# Logic.net
KiCad netlist of a schematic drawn in EAGLE
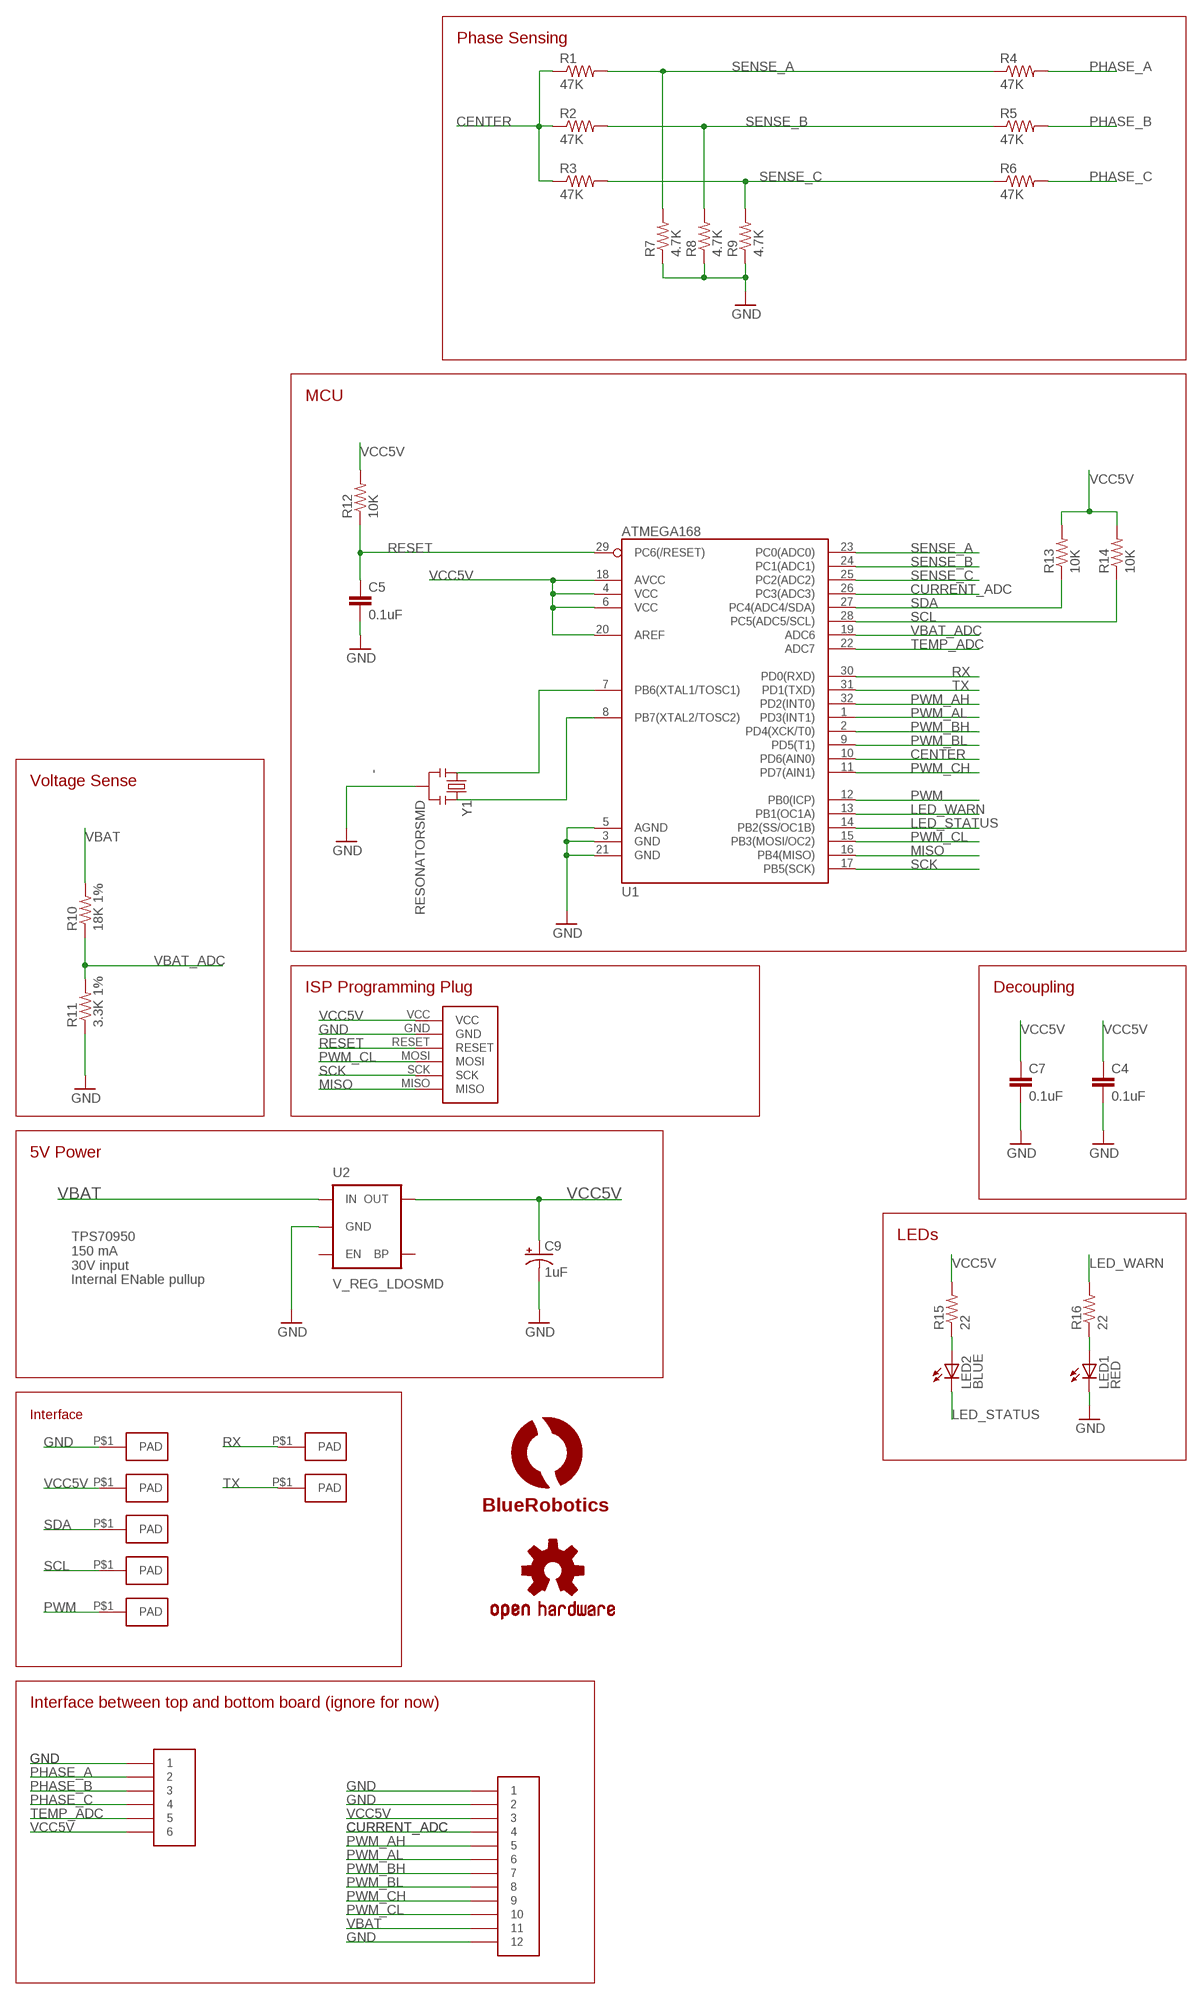
[diagram p0: schematic, sheet 1]

(export (version "E")
  (design (tool "Eeschema 10.0.6"))
  (components
    (comp (ref "C4")
      (value "0.1uF")
      (footprint "eagle-import:0603-CAP")
      (libsource (lib "eagle-import") (part "CAP0603-CAP"))
    )
    (comp (ref "C5")
      (value "0.1uF")
      (footprint "eagle-import:0603-CAP")
      (libsource (lib "eagle-import") (part "CAP0603-CAP"))
    )
    (comp (ref "C7")
      (value "0.1uF")
      (footprint "eagle-import:0603-CAP")
      (libsource (lib "eagle-import") (part "CAP0603-CAP"))
    )
    (comp (ref "C9")
      (value "1uF")
      (footprint "eagle-import:EIA3216")
      (libsource (lib "eagle-import") (part "CAP_POL1206"))
    )
    (comp (ref "LED1")
      (value "RED")
      (footprint "eagle-import:LED3MM-NS")
      (libsource (lib "eagle-import") (part "LED-3MM-NO_SILK"))
    )
    (comp (ref "LED2")
      (value "BLUE")
      (footprint "eagle-import:LED3MM-NS")
      (libsource (lib "eagle-import") (part "LED-3MM-NO_SILK"))
    )
    (comp (ref "LOGO1")
      (value "OSHW-LOGOS")
      (footprint "eagle-import:OSHW-LOGO-S")
      (libsource (lib "eagle-import") (part "OSHW-LOGOS"))
    )
    (comp (ref "R1")
      (value "47K")
      (footprint "eagle-import:0603-RES")
      (libsource (lib "eagle-import") (part "33KOHM1/10W1%(0603)"))
    )
    (comp (ref "R2")
      (value "47K")
      (footprint "eagle-import:0603-RES")
      (libsource (lib "eagle-import") (part "33KOHM1/10W1%(0603)"))
    )
    (comp (ref "R3")
      (value "47K")
      (footprint "eagle-import:0603-RES")
      (libsource (lib "eagle-import") (part "33KOHM1/10W1%(0603)"))
    )
    (comp (ref "R4")
      (value "47K")
      (footprint "eagle-import:0603-RES")
      (libsource (lib "eagle-import") (part "33KOHM1/10W1%(0603)"))
    )
    (comp (ref "R5")
      (value "47K")
      (footprint "eagle-import:0603-RES")
      (libsource (lib "eagle-import") (part "33KOHM1/10W1%(0603)"))
    )
    (comp (ref "R6")
      (value "47K")
      (footprint "eagle-import:0603-RES")
      (libsource (lib "eagle-import") (part "33KOHM1/10W1%(0603)"))
    )
    (comp (ref "R7")
      (value "4.7K")
      (footprint "eagle-import:0603-RES")
      (libsource (lib "eagle-import") (part "RESISTOR0603"))
    )
    (comp (ref "R8")
      (value "4.7K")
      (footprint "eagle-import:0603-RES")
      (libsource (lib "eagle-import") (part "RESISTOR0603"))
    )
    (comp (ref "R9")
      (value "4.7K")
      (footprint "eagle-import:0603-RES")
      (libsource (lib "eagle-import") (part "RESISTOR0603"))
    )
    (comp (ref "R10")
      (value "18K 1%")
      (footprint "eagle-import:0603-RES")
      (libsource (lib "eagle-import") (part "33KOHM1/10W1%(0603)"))
    )
    (comp (ref "R11")
      (value "3.3K 1%")
      (footprint "eagle-import:0603-RES")
      (libsource (lib "eagle-import") (part "33KOHM1/10W1%(0603)"))
    )
    (comp (ref "R12")
      (value "10K")
      (footprint "eagle-import:0603-RES")
      (libsource (lib "eagle-import") (part "33KOHM1/10W1%(0603)"))
    )
    (comp (ref "R13")
      (value "10K")
      (footprint "eagle-import:0603-RES")
      (libsource (lib "eagle-import") (part "33KOHM1/10W1%(0603)"))
    )
    (comp (ref "R14")
      (value "10K")
      (footprint "eagle-import:0603-RES")
      (libsource (lib "eagle-import") (part "33KOHM1/10W1%(0603)"))
    )
    (comp (ref "R15")
      (value "22")
      (footprint "eagle-import:0603-RES")
      (libsource (lib "eagle-import") (part "RESISTOR0603-RES"))
    )
    (comp (ref "R16")
      (value "22")
      (footprint "eagle-import:0603-RES")
      (libsource (lib "eagle-import") (part "RESISTOR0603-RES"))
    )
    (comp (ref "U$3")
      (value "PAD1.5X3MM")
      (footprint "eagle-import:PAD-1.5X3MM")
      (libsource (lib "eagle-import") (part "PAD1.5X3MM"))
    )
    (comp (ref "U$4")
      (value "LOGOBR-LOGO-S")
      (footprint "eagle-import:BR-LOGO-SMALL")
      (libsource (lib "eagle-import") (part "LOGOBR-LOGO-S"))
    )
    (comp (ref "U$8")
      (value "PAD1.5X3MM")
      (footprint "eagle-import:PAD-1.5X3MM")
      (libsource (lib "eagle-import") (part "PAD1.5X3MM"))
    )
    (comp (ref "U$9")
      (value "PAD1.5X3MM")
      (footprint "eagle-import:PAD-1.5X3MM")
      (libsource (lib "eagle-import") (part "PAD1.5X3MM"))
    )
    (comp (ref "U$10")
      (value "PAD1.5X3MM")
      (footprint "eagle-import:PAD-1.5X3MM")
      (libsource (lib "eagle-import") (part "PAD1.5X3MM"))
    )
    (comp (ref "U$11")
      (value "PAD1.5X3MM")
      (footprint "eagle-import:PAD-1.5X3MM")
      (libsource (lib "eagle-import") (part "PAD1.5X3MM"))
    )
    (comp (ref "U$12")
      (value "PAD1.5X3MM")
      (footprint "eagle-import:PAD-1.5X3MM")
      (libsource (lib "eagle-import") (part "PAD1.5X3MM"))
    )
    (comp (ref "U$13")
      (value "PAD1.5X3MM")
      (footprint "eagle-import:PAD-1.5X3MM")
      (libsource (lib "eagle-import") (part "PAD1.5X3MM"))
    )
    (comp (ref "U$14")
      (value "AVR-ISPTINY-SMD")
      (footprint "eagle-import:AVR-ISP-TINY")
      (libsource (lib "eagle-import") (part "AVR-ISPTINY-SMD"))
    )
    (comp (ref "U$16")
      (value "HEADER-62MM")
      (footprint "eagle-import:HEADER-2MM-6POS")
      (libsource (lib "eagle-import") (part "HEADER-62MM"))
    )
    (comp (ref "U$17")
      (value "HEADER-122MM")
      (footprint "eagle-import:HEADER-2MM-12POS")
      (libsource (lib "eagle-import") (part "HEADER-122MM"))
    )
    (comp (ref "U1")
      (value "ATMEGA168")
      (footprint "eagle-import:TQFP32-08")
      (libsource (lib "eagle-import") (part "ATMEGA168"))
    )
    (comp (ref "U2")
      (value "V_REG_LDOSMD")
      (footprint "eagle-import:SOT23-5")
      (libsource (lib "eagle-import") (part "V_REG_LDOSMD"))
    )
    (comp (ref "Y1")
      (value "RESONATORSMD")
      (footprint "eagle-import:RESONATOR-SMD")
      (libsource (lib "eagle-import") (part "RESONATORSMD"))
    )
  )
  (nets
    (net (code "1") (name "/CENTER") (class "Default")
      (node (ref "R1") (pin "1") (pinfunction "1_1") (pintype "passive"))
      (node (ref "R2") (pin "1") (pinfunction "1_1") (pintype "passive"))
      (node (ref "R3") (pin "1") (pinfunction "1_1") (pintype "passive"))
      (node (ref "U1") (pin "10") (pinfunction "PD6(AIN0)_10") (pintype "bidirectional"))
    )
    (net (code "2") (name "/CURRENT_ADC") (class "Default")
      (node (ref "U$17") (pin "P$4") (pinfunction "4_P$4") (pintype "bidirectional"))
      (node (ref "U1") (pin "26") (pinfunction "PC3(ADC3)_26") (pintype "bidirectional"))
    )
    (net (code "3") (name "/LED_STATUS") (class "Default")
      (node (ref "LED2") (pin "K") (pinfunction "C_K") (pintype "passive"))
      (node (ref "U1") (pin "14") (pinfunction "PB2(SS/OC1B)_14") (pintype "bidirectional"))
    )
    (net (code "4") (name "/LED_WARN") (class "Default")
      (node (ref "R16") (pin "2") (pinfunction "2_2") (pintype "passive"))
      (node (ref "U1") (pin "13") (pinfunction "PB1(OC1A)_13") (pintype "bidirectional"))
    )
    (net (code "5") (name "/MISO") (class "Default")
      (node (ref "U$14") (pin "MISO") (pinfunction "MISO_MISO") (pintype "bidirectional"))
      (node (ref "U1") (pin "16") (pinfunction "PB4(MISO)_16") (pintype "bidirectional"))
    )
    (net (code "6") (name "/PHASE_A") (class "Default")
      (node (ref "R4") (pin "2") (pinfunction "2_2") (pintype "passive"))
      (node (ref "U$16") (pin "P$2") (pinfunction "2_P$2") (pintype "bidirectional"))
    )
    (net (code "7") (name "/PHASE_B") (class "Default")
      (node (ref "R5") (pin "2") (pinfunction "2_2") (pintype "passive"))
      (node (ref "U$16") (pin "P$3") (pinfunction "3_P$3") (pintype "bidirectional"))
    )
    (net (code "8") (name "/PHASE_C") (class "Default")
      (node (ref "R6") (pin "2") (pinfunction "2_2") (pintype "passive"))
      (node (ref "U$16") (pin "P$4") (pinfunction "4_P$4") (pintype "bidirectional"))
    )
    (net (code "9") (name "/PWM") (class "Default")
      (node (ref "U$11") (pin "P$1") (pinfunction "PAD_P$1") (pintype "bidirectional"))
      (node (ref "U1") (pin "12") (pinfunction "PB0(ICP)_12") (pintype "bidirectional"))
    )
    (net (code "10") (name "/PWM_AH") (class "Default")
      (node (ref "U$17") (pin "P$5") (pinfunction "5_P$5") (pintype "bidirectional"))
      (node (ref "U1") (pin "32") (pinfunction "PD2(INT0)_32") (pintype "bidirectional"))
    )
    (net (code "11") (name "/PWM_AL") (class "Default")
      (node (ref "U$17") (pin "P$6") (pinfunction "6_P$6") (pintype "bidirectional"))
      (node (ref "U1") (pin "1") (pinfunction "PD3(INT1)_1") (pintype "bidirectional"))
    )
    (net (code "12") (name "/PWM_BH") (class "Default")
      (node (ref "U$17") (pin "P$7") (pinfunction "7_P$7") (pintype "bidirectional"))
      (node (ref "U1") (pin "2") (pinfunction "PD4(XCK/T0)_2") (pintype "bidirectional"))
    )
    (net (code "13") (name "/PWM_BL") (class "Default")
      (node (ref "U$17") (pin "P$8") (pinfunction "8_P$8") (pintype "bidirectional"))
      (node (ref "U1") (pin "9") (pinfunction "PD5(T1)_9") (pintype "bidirectional"))
    )
    (net (code "14") (name "/PWM_CH") (class "Default")
      (node (ref "U$17") (pin "P$9") (pinfunction "9_P$9") (pintype "bidirectional"))
      (node (ref "U1") (pin "11") (pinfunction "PD7(AIN1)_11") (pintype "bidirectional"))
    )
    (net (code "15") (name "/PWM_CL") (class "Default")
      (node (ref "U$14") (pin "MOSI") (pinfunction "MOSI_MOSI") (pintype "bidirectional"))
      (node (ref "U$17") (pin "P$10") (pinfunction "10_P$10") (pintype "bidirectional"))
      (node (ref "U1") (pin "15") (pinfunction "PB3(MOSI/OC2)_15") (pintype "bidirectional"))
    )
    (net (code "16") (name "/RESET") (class "Default")
      (node (ref "C5") (pin "1") (pinfunction "1_1") (pintype "passive"))
      (node (ref "R12") (pin "1") (pinfunction "1_1") (pintype "passive"))
      (node (ref "U$14") (pin "RESET") (pinfunction "RESET_RESET") (pintype "bidirectional"))
      (node (ref "U1") (pin "29") (pinfunction "PC6(/RESET)_29") (pintype "bidirectional"))
    )
    (net (code "17") (name "/RX") (class "Default")
      (node (ref "U$12") (pin "P$1") (pinfunction "PAD_P$1") (pintype "bidirectional"))
      (node (ref "U1") (pin "30") (pinfunction "PD0(RXD)_30") (pintype "bidirectional"))
    )
    (net (code "18") (name "/SCK") (class "Default")
      (node (ref "U$14") (pin "SCK") (pinfunction "SCK_SCK") (pintype "bidirectional"))
      (node (ref "U1") (pin "17") (pinfunction "PB5(SCK)_17") (pintype "bidirectional"))
    )
    (net (code "19") (name "/SCL") (class "Default")
      (node (ref "R14") (pin "1") (pinfunction "1_1") (pintype "passive"))
      (node (ref "U$10") (pin "P$1") (pinfunction "PAD_P$1") (pintype "bidirectional"))
      (node (ref "U1") (pin "28") (pinfunction "PC5(ADC5/SCL)_28") (pintype "bidirectional"))
    )
    (net (code "20") (name "/SDA") (class "Default")
      (node (ref "R13") (pin "1") (pinfunction "1_1") (pintype "passive"))
      (node (ref "U$9") (pin "P$1") (pinfunction "PAD_P$1") (pintype "bidirectional"))
      (node (ref "U1") (pin "27") (pinfunction "PC4(ADC4/SDA)_27") (pintype "bidirectional"))
    )
    (net (code "21") (name "/SENSE_A") (class "Default")
      (node (ref "R1") (pin "2") (pinfunction "2_2") (pintype "passive"))
      (node (ref "R4") (pin "1") (pinfunction "1_1") (pintype "passive"))
      (node (ref "R7") (pin "2") (pinfunction "2_2") (pintype "passive"))
      (node (ref "U1") (pin "23") (pinfunction "PC0(ADC0)_23") (pintype "bidirectional"))
    )
    (net (code "22") (name "/SENSE_B") (class "Default")
      (node (ref "R2") (pin "2") (pinfunction "2_2") (pintype "passive"))
      (node (ref "R5") (pin "1") (pinfunction "1_1") (pintype "passive"))
      (node (ref "R8") (pin "2") (pinfunction "2_2") (pintype "passive"))
      (node (ref "U1") (pin "24") (pinfunction "PC1(ADC1)_24") (pintype "bidirectional"))
    )
    (net (code "23") (name "/SENSE_C") (class "Default")
      (node (ref "R3") (pin "2") (pinfunction "2_2") (pintype "passive"))
      (node (ref "R6") (pin "1") (pinfunction "1_1") (pintype "passive"))
      (node (ref "R9") (pin "2") (pinfunction "2_2") (pintype "passive"))
      (node (ref "U1") (pin "25") (pinfunction "PC2(ADC2)_25") (pintype "bidirectional"))
    )
    (net (code "24") (name "/TEMP_ADC") (class "Default")
      (node (ref "U$16") (pin "P$5") (pinfunction "5_P$5") (pintype "bidirectional"))
      (node (ref "U1") (pin "22") (pinfunction "ADC7_22") (pintype "bidirectional"))
    )
    (net (code "25") (name "/TX") (class "Default")
      (node (ref "U$13") (pin "P$1") (pinfunction "PAD_P$1") (pintype "bidirectional"))
      (node (ref "U1") (pin "31") (pinfunction "PD1(TXD)_31") (pintype "bidirectional"))
    )
    (net (code "26") (name "/VBAT") (class "Default")
      (node (ref "R10") (pin "2") (pinfunction "2_2") (pintype "passive"))
      (node (ref "U$17") (pin "P$11") (pinfunction "11_P$11") (pintype "bidirectional"))
      (node (ref "U2") (pin "1") (pinfunction "IN_1") (pintype "input"))
    )
    (net (code "27") (name "/VBAT_ADC") (class "Default")
      (node (ref "R10") (pin "1") (pinfunction "1_1") (pintype "passive"))
      (node (ref "R11") (pin "2") (pinfunction "2_2") (pintype "passive"))
      (node (ref "U1") (pin "19") (pinfunction "ADC6_19") (pintype "bidirectional"))
    )
    (net (code "28") (name "/VCC5V") (class "Default")
      (node (ref "C4") (pin "1") (pinfunction "1_1") (pintype "passive"))
      (node (ref "C7") (pin "1") (pinfunction "1_1") (pintype "passive"))
      (node (ref "C9") (pin "A") (pinfunction "+_A") (pintype "passive"))
      (node (ref "R12") (pin "2") (pinfunction "2_2") (pintype "passive"))
      (node (ref "R13") (pin "2") (pinfunction "2_2") (pintype "passive"))
      (node (ref "R14") (pin "2") (pinfunction "2_2") (pintype "passive"))
      (node (ref "R15") (pin "2") (pinfunction "2_2") (pintype "passive"))
      (node (ref "U$14") (pin "VCC") (pinfunction "VCC_VCC") (pintype "power_in"))
      (node (ref "U$16") (pin "P$6") (pinfunction "6_P$6") (pintype "bidirectional"))
      (node (ref "U$17") (pin "P$3") (pinfunction "3_P$3") (pintype "bidirectional"))
      (node (ref "U$8") (pin "P$1") (pinfunction "PAD_P$1") (pintype "bidirectional"))
      (node (ref "U1") (pin "18") (pinfunction "AVCC_18") (pintype "bidirectional"))
      (node (ref "U1") (pin "20") (pinfunction "AREF_20") (pintype "bidirectional"))
      (node (ref "U1") (pin "4") (pinfunction "VCC_4") (pintype "bidirectional"))
      (node (ref "U1") (pin "6") (pinfunction "VCC_6") (pintype "bidirectional"))
      (node (ref "U2") (pin "5") (pinfunction "OUT_5") (pintype "passive"))
    )
    (net (code "29") (name "GND") (class "Default")
      (node (ref "C4") (pin "2") (pinfunction "2_2") (pintype "passive"))
      (node (ref "C5") (pin "2") (pinfunction "2_2") (pintype "passive"))
      (node (ref "C7") (pin "2") (pinfunction "2_2") (pintype "passive"))
      (node (ref "C9") (pin "C") (pinfunction "-_C") (pintype "passive"))
      (node (ref "LED1") (pin "K") (pinfunction "C_K") (pintype "passive"))
      (node (ref "R11") (pin "1") (pinfunction "1_1") (pintype "passive"))
      (node (ref "R7") (pin "1") (pinfunction "1_1") (pintype "passive"))
      (node (ref "R8") (pin "1") (pinfunction "1_1") (pintype "passive"))
      (node (ref "R9") (pin "1") (pinfunction "1_1") (pintype "passive"))
      (node (ref "U$14") (pin "GND") (pinfunction "GND_GND") (pintype "power_in"))
      (node (ref "U$16") (pin "P$1") (pinfunction "1_P$1") (pintype "bidirectional"))
      (node (ref "U$17") (pin "P$1") (pinfunction "1_P$1") (pintype "bidirectional"))
      (node (ref "U$17") (pin "P$12") (pinfunction "12_P$12") (pintype "bidirectional"))
      (node (ref "U$17") (pin "P$2") (pinfunction "2_P$2") (pintype "bidirectional"))
      (node (ref "U$3") (pin "P$1") (pinfunction "PAD_P$1") (pintype "bidirectional"))
      (node (ref "U1") (pin "21") (pinfunction "GND_21") (pintype "bidirectional"))
      (node (ref "U1") (pin "3") (pinfunction "GND_3") (pintype "bidirectional"))
      (node (ref "U1") (pin "5") (pinfunction "AGND_5") (pintype "bidirectional"))
      (node (ref "U2") (pin "2") (pinfunction "GND_2") (pintype "input"))
      (node (ref "Y1") (pin "2") (pinfunction "2_2") (pintype "passive"))
    )
    (net (code "30") (name "Net-(LED1-PadA)") (class "Default")
      (node (ref "LED1") (pin "A") (pinfunction "A_A") (pintype "passive"))
      (node (ref "R16") (pin "1") (pinfunction "1_1") (pintype "passive"))
    )
    (net (code "31") (name "Net-(LED2-PadA)") (class "Default")
      (node (ref "LED2") (pin "A") (pinfunction "A_A") (pintype "passive"))
      (node (ref "R15") (pin "1") (pinfunction "1_1") (pintype "passive"))
    )
    (net (code "32") (name "Net-(U1-PB6(XTAL1{slash}TOSC1))") (class "Default")
      (node (ref "U1") (pin "7") (pinfunction "PB6(XTAL1/TOSC1)_7") (pintype "bidirectional"))
      (node (ref "Y1") (pin "1") (pinfunction "1_1") (pintype "passive"))
    )
    (net (code "33") (name "Net-(U1-PB7(XTAL2{slash}TOSC2))") (class "Default")
      (node (ref "U1") (pin "8") (pinfunction "PB7(XTAL2/TOSC2)_8") (pintype "bidirectional"))
      (node (ref "Y1") (pin "3") (pinfunction "3_3") (pintype "passive"))
    )
    (net (code "34") (name "unconnected-(U2-BP-Pad4)") (class "Default")
      (node (ref "U2") (pin "4") (pinfunction "BP_4") (pintype "input"))
    )
    (net (code "35") (name "unconnected-(U2-EN-Pad3)") (class "Default")
      (node (ref "U2") (pin "3") (pinfunction "EN_3") (pintype "input"))
    )
  )
)
